# mp3412-boost-driver-15mm-mk-1_0.net
KiCad netlist of a schematic drawn in EAGLE
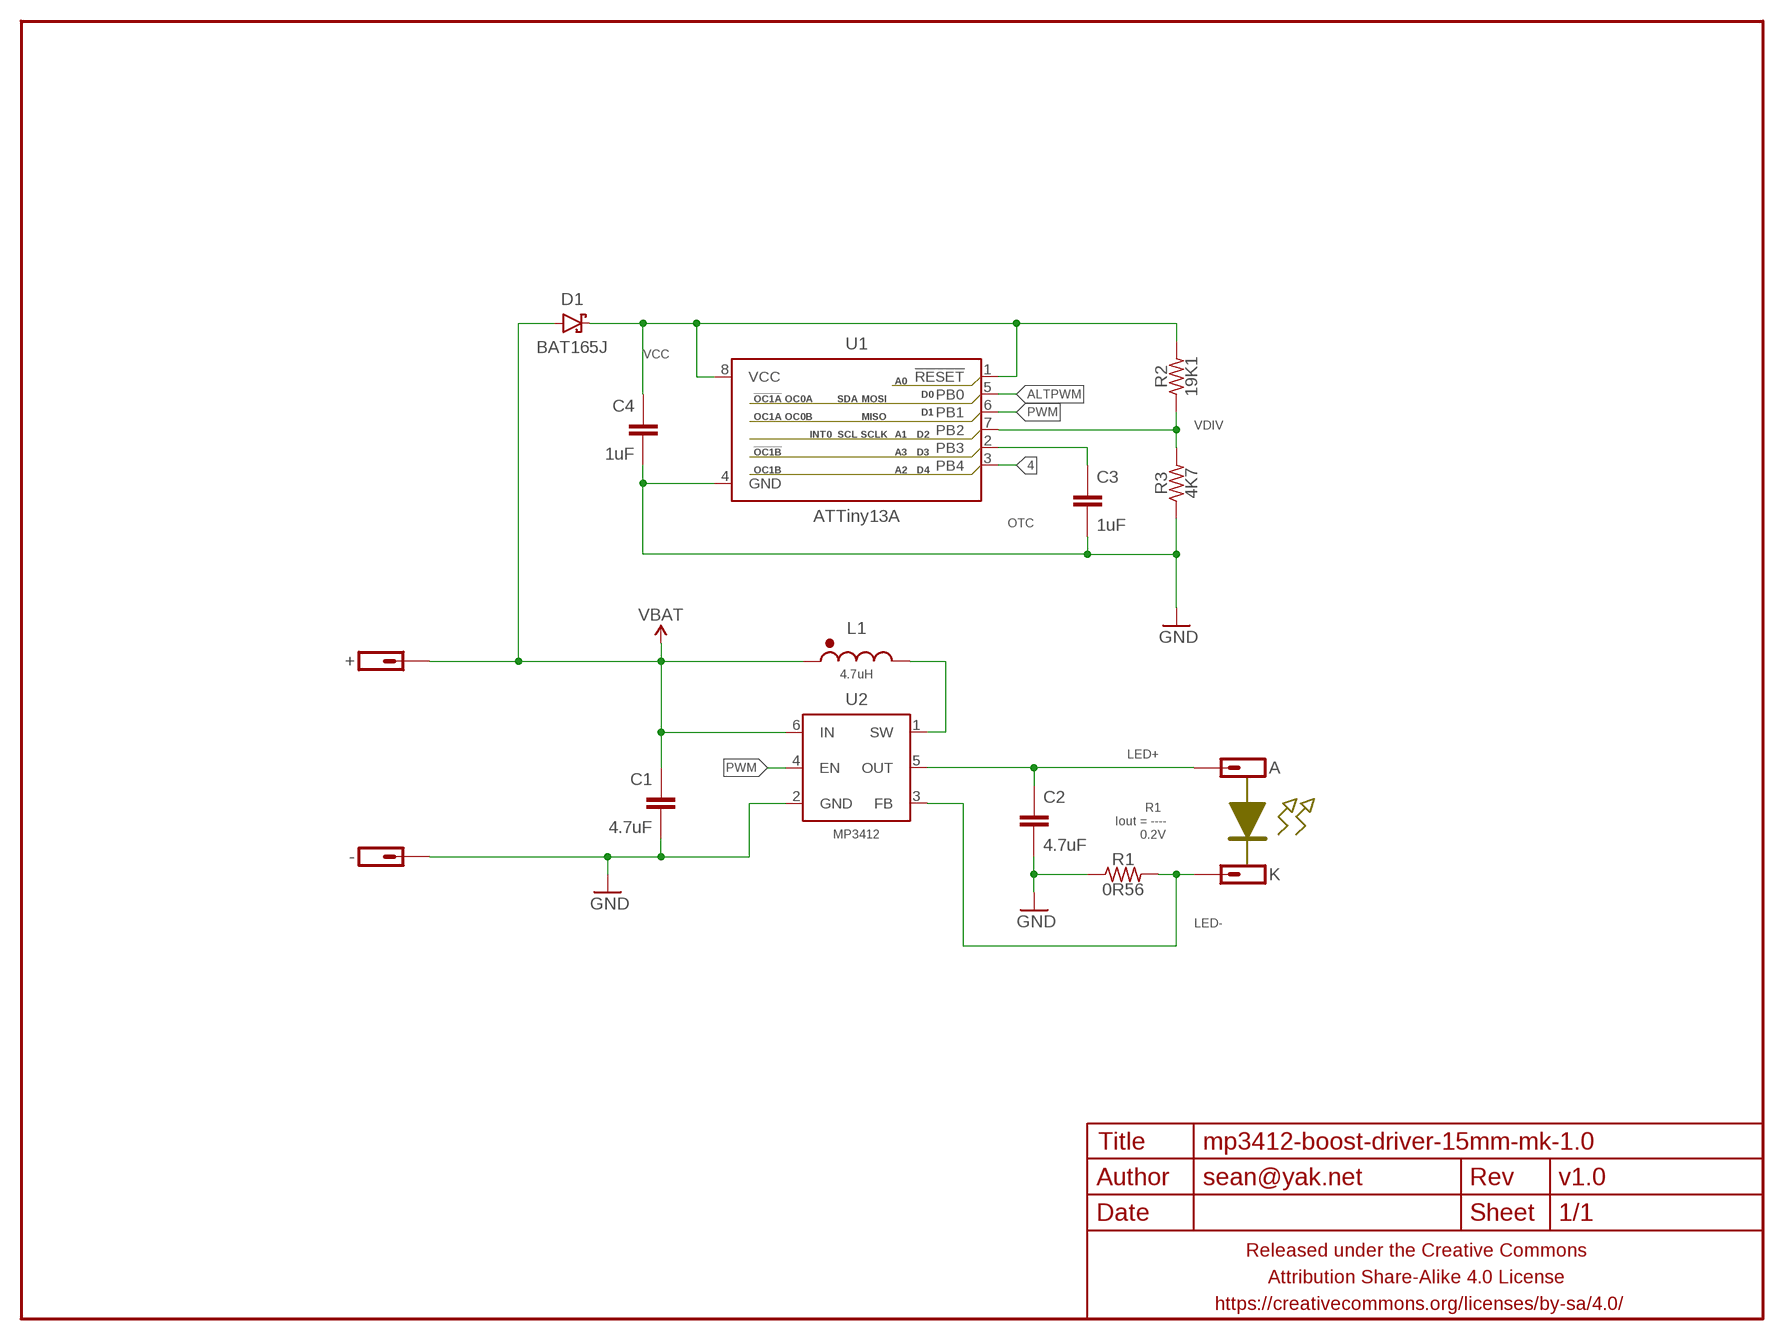
[diagram p0: schematic, sheet 1]

(export (version "E")
  (design (tool "Eeschema 10.0.6"))
  (components
    (comp (ref "+")
      (value "M01PTH-1MM-CIR-NS")
      (footprint "eagle-import:1X01-1MM-CIR-NS")
      (libsource (lib "eagle-import") (part "M01PTH-1MM-CIR-NS"))
    )
    (comp (ref "-")
      (value "M01NOT-A-VIA-NOPE")
      (footprint "eagle-import:1X01_NOSILK_NOSTOP")
      (libsource (lib "eagle-import") (part "M01NOT-A-VIA-NOPE"))
    )
    (comp (ref "A")
      (value "M01SMD-1.25MM-DIA")
      (footprint "eagle-import:1X01-SMD-1.25MM-DIA-NS")
      (libsource (lib "eagle-import") (part "M01SMD-1.25MM-DIA"))
    )
    (comp (ref "C1")
      (value "4.7uF")
      (footprint "eagle-import:C0603-TIGHTER")
      (libsource (lib "eagle-import") (part "CAPACITOR-CERAMICC0603-TIGHTER"))
    )
    (comp (ref "C2")
      (value "4.7uF")
      (footprint "eagle-import:C0603-TIGHTER")
      (libsource (lib "eagle-import") (part "CAPACITOR-CERAMICC0603-TIGHTER"))
    )
    (comp (ref "C3")
      (value "1uF")
      (footprint "eagle-import:C0402")
      (libsource (lib "eagle-import") (part "CAPACITOR-CERAMICC0402"))
    )
    (comp (ref "C4")
      (value "1uF")
      (footprint "eagle-import:C0402")
      (libsource (lib "eagle-import") (part "CAPACITOR-CERAMICC0402"))
    )
    (comp (ref "D1")
      (value "BAT165J")
      (footprint "eagle-import:SOD323-SCHOTTKY")
      (libsource (lib "eagle-import") (part "DIODE-SCHOTTKYSOD323"))
    )
    (comp (ref "FRAME1")
      (value "FRAME-LETTERNO_PACKAGE")
      (footprint "eagle-import:DUMMY")
      (fields (field (name "DESIGNER") "sean@yak.net") (field (name "VERSION") "v1.0"))
      (libsource (lib "eagle-import") (part "FRAME-LETTERNO_PACKAGE"))
    )
    (comp (ref "K")
      (value "M01SMD-1.25MM-DIA")
      (footprint "eagle-import:1X01-SMD-1.25MM-DIA-NS")
      (libsource (lib "eagle-import") (part "M01SMD-1.25MM-DIA"))
    )
    (comp (ref "L1")
      (value "4.7uH")
      (footprint "eagle-import:LPS4012-ROUND")
      (libsource (lib "eagle-import") (part "INDUCTORLPS4012-ROUND-PADS"))
    )
    (comp (ref "R1")
      (value "0R56")
      (footprint "eagle-import:R0603-TIGHTER")
      (libsource (lib "eagle-import") (part "RESISTORR0603-TIGHTER"))
    )
    (comp (ref "R2")
      (value "19K1")
      (footprint "eagle-import:R0402")
      (libsource (lib "eagle-import") (part "RESISTORR0402"))
    )
    (comp (ref "R3")
      (value "4K7")
      (footprint "eagle-import:R0402")
      (libsource (lib "eagle-import") (part "RESISTORR0402"))
    )
    (comp (ref "U1")
      (value "ATTiny13A")
      (footprint "eagle-import:SO08-NARROWER")
      (libsource (lib "eagle-import") (part "ATTINY13SOIC-NARROWPADS"))
    )
    (comp (ref "U2")
      (value "MP3412")
      (footprint "eagle-import:TSOT-23-6")
      (libsource (lib "eagle-import") (part "MP3412"))
    )
  )
  (nets
    (net (code "1") (name "/LED+") (class "Default")
      (node (ref "A") (pin "P$1") (pinfunction "1_P$1") (pintype "passive"))
      (node (ref "C2") (pin "1") (pinfunction "1_1") (pintype "passive"))
      (node (ref "U2") (pin "5") (pinfunction "OUT_5") (pintype "bidirectional"))
    )
    (net (code "2") (name "/LED-") (class "Default")
      (node (ref "K") (pin "P$1") (pinfunction "1_P$1") (pintype "passive"))
      (node (ref "R1") (pin "2") (pinfunction "2_2") (pintype "passive"))
      (node (ref "U2") (pin "3") (pinfunction "FB_3") (pintype "bidirectional"))
    )
    (net (code "3") (name "/VCC") (class "Default")
      (node (ref "C4") (pin "1") (pinfunction "1_1") (pintype "passive"))
      (node (ref "D1") (pin "C") (pinfunction "C_C") (pintype "passive"))
      (node (ref "R2") (pin "2") (pinfunction "2_2") (pintype "passive"))
      (node (ref "U1") (pin "1") (pinfunction "~{RESET}_1") (pintype "bidirectional"))
      (node (ref "U1") (pin "8") (pinfunction "VCC_8") (pintype "bidirectional"))
    )
    (net (code "4") (name "/VDIV") (class "Default")
      (node (ref "R2") (pin "1") (pinfunction "1_1") (pintype "passive"))
      (node (ref "R3") (pin "2") (pinfunction "2_2") (pintype "passive"))
      (node (ref "U1") (pin "7") (pinfunction "PB2_7") (pintype "bidirectional"))
    )
    (net (code "5") (name "4") (class "Default")
      (node (ref "U1") (pin "3") (pinfunction "PB4_3") (pintype "bidirectional"))
    )
    (net (code "6") (name "ALTPWM") (class "Default")
      (node (ref "U1") (pin "5") (pinfunction "PB0_5") (pintype "bidirectional"))
    )
    (net (code "7") (name "GND") (class "Default")
      (node (ref "-") (pin "P$1") (pinfunction "1_P$1") (pintype "passive"))
      (node (ref "C1") (pin "2") (pinfunction "2_2") (pintype "passive"))
      (node (ref "C2") (pin "2") (pinfunction "2_2") (pintype "passive"))
      (node (ref "C3") (pin "2") (pinfunction "2_2") (pintype "passive"))
      (node (ref "C4") (pin "2") (pinfunction "2_2") (pintype "passive"))
      (node (ref "R1") (pin "1") (pinfunction "1_1") (pintype "passive"))
      (node (ref "R3") (pin "1") (pinfunction "1_1") (pintype "passive"))
      (node (ref "U1") (pin "4") (pinfunction "GND_4") (pintype "bidirectional"))
      (node (ref "U2") (pin "2") (pinfunction "GND_2") (pintype "bidirectional"))
    )
    (net (code "8") (name "Net-(L1-2)") (class "Default")
      (node (ref "L1") (pin "P$2") (pinfunction "2_P$2") (pintype "passive"))
      (node (ref "U2") (pin "1") (pinfunction "SW_1") (pintype "bidirectional"))
    )
    (net (code "9") (name "Net-(U1-PB3)") (class "Default")
      (node (ref "C3") (pin "1") (pinfunction "1_1") (pintype "passive"))
      (node (ref "U1") (pin "2") (pinfunction "PB3_2") (pintype "bidirectional"))
    )
    (net (code "10") (name "PWM") (class "Default")
      (node (ref "U1") (pin "6") (pinfunction "PB1_6") (pintype "bidirectional"))
      (node (ref "U2") (pin "4") (pinfunction "EN_4") (pintype "bidirectional"))
    )
    (net (code "11") (name "VBAT") (class "Default")
      (node (ref "+") (pin "1") (pinfunction "1_1") (pintype "passive"))
      (node (ref "C1") (pin "1") (pinfunction "1_1") (pintype "passive"))
      (node (ref "D1") (pin "A") (pinfunction "A_A") (pintype "passive"))
      (node (ref "L1") (pin "P$1") (pinfunction "1_P$1") (pintype "passive"))
      (node (ref "U2") (pin "6") (pinfunction "IN_6") (pintype "bidirectional"))
    )
  )
)
